# 16-ECP5_FPGA_1.net
KiCad netlist of a schematic drawn in Altium Designer
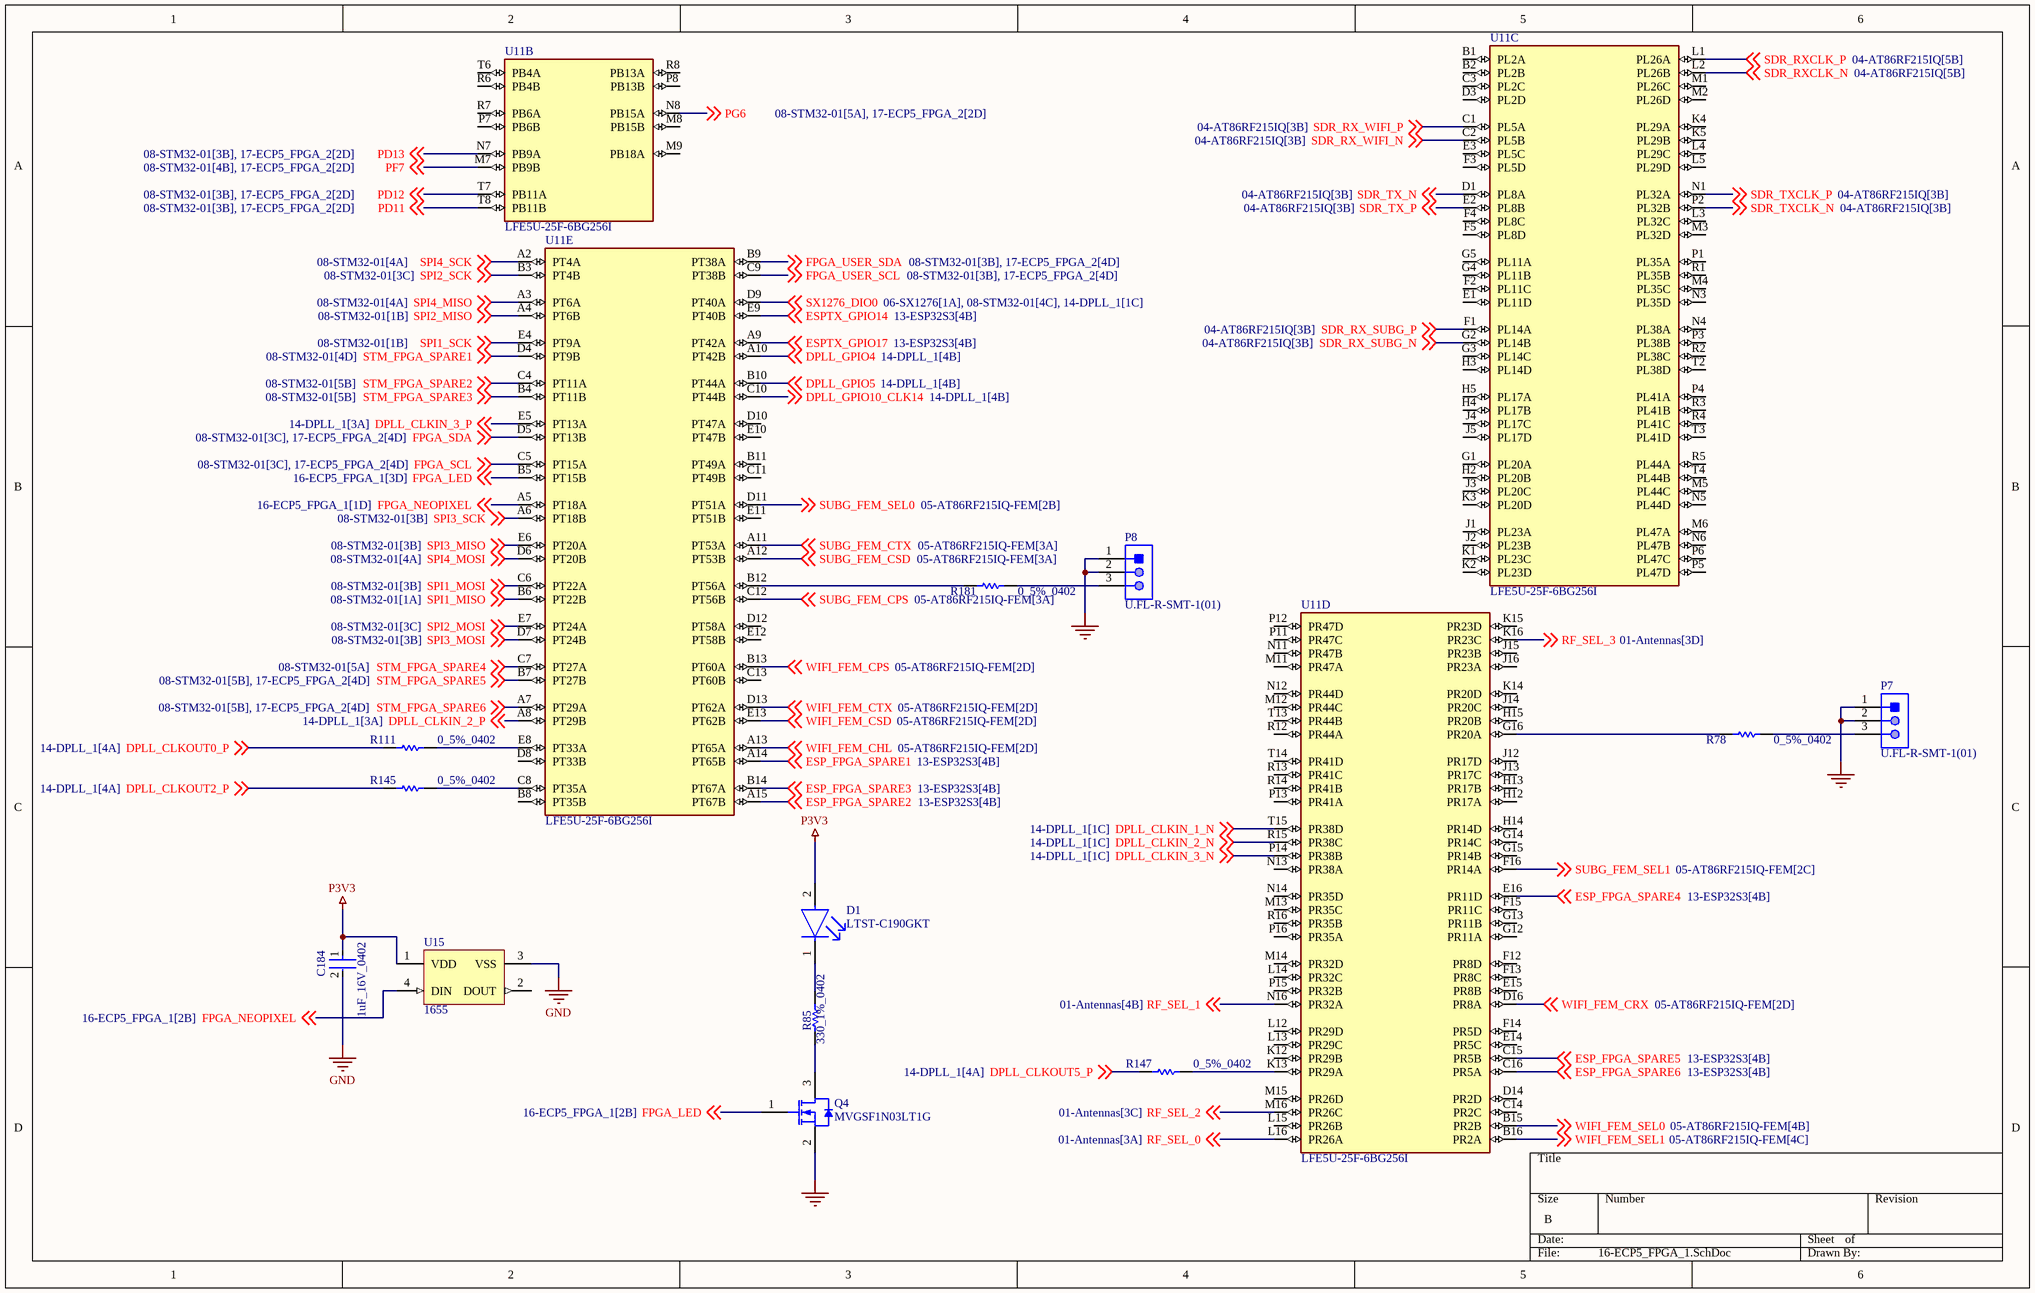
[diagram p0: 16-ECP5_FPGA_1.SchDoc]

(export (version "E")
  (design (tool "Eeschema 10.0.6"))
  (components
    (comp (ref "C184")
      (value "1uF_16V_0402")
      (footprint "FP-0402-L_1_0_0_05-W_0_5-IPC_A")
      (description "None")
      (fields (field (name "TOLERANCE") "10%"))
      (libsource (lib "Altium Content Vault") (part "b4654b650e69147ec39a6b967a45e02"))
    )
    (comp (ref "D1")
      (value "LTST-C190GKT")
      (footprint "FP-LTST-C190GKT-MFG")
      (description "LED GREEN CLEAR CHIP SMD")
      (fields (field (name "VOLTAGE") "2V"))
      (libsource (lib "Altium Content Vault") (part "8706943c75ba83719d021d2fdc84c58"))
    )
    (comp (ref "P7")
      (value "U.FL-R-SMT-1(01)")
      (footprint "HRS-U.FL-R-SMT-3_V")
      (description "Ultra Small Coaxial Connector, 6 GHz, -40 to 90 degC, 3-Pin SMD, RoHS, Bulk")
      (fields (field (name "MANUFACTURER") "Hirose Electric"))
      (libsource (lib "Altium Content Vault") (part "CN-1P-M-R3"))
    )
    (comp (ref "P8")
      (value "U.FL-R-SMT-1(01)")
      (footprint "HRS-U.FL-R-SMT-3_V")
      (description "Ultra Small Coaxial Connector, 6 GHz, -40 to 90 degC, 3-Pin SMD, RoHS, Bulk")
      (fields (field (name "MANUFACTURER") "Hirose Electric"))
      (libsource (lib "Altium Content Vault") (part "CN-1P-M-R3"))
    )
    (comp (ref "Q4")
      (value "MVGSF1N03LT1G")
      (footprint "ONSC-SOT-23-3-318-08_V")
      (description "Power MOSFET, 30 V, 2.1 A, Single N-Channel, 3-Pin SOT-23, Pb-Free, Tape and Reel")
      (fields (field (name "MANUFACTURER") "On Semiconductor"))
      (libsource (lib "Altium Content Vault") (part "ONSC-NMOS-G1S2D3-3"))
    )
    (comp (ref "R78")
      (value "0_5%_0402")
      (footprint "RESC1005X40X25NL05T10")
      (fields (field (name "MANUFACTURER") "Panasonic") (field (name "PART NUMBER") "ERJ-U020R00X"))
      (libsource (lib "Altium Content Vault") (part "RES"))
    )
    (comp (ref "R85")
      (value "330_1%_0402")
      (footprint "RESC1005X40X25NL10T10")
      (fields (field (name "MANUFACTURER") "Panasonic") (field (name "PART NUMBER") "ERA-2AED331X"))
      (libsource (lib "Altium Content Vault") (part "RES"))
    )
    (comp (ref "R111")
      (value "0_5%_0402")
      (footprint "RESC1005X40X25NL05T10")
      (fields (field (name "MANUFACTURER") "Panasonic") (field (name "PART NUMBER") "ERJ-U020R00X"))
      (libsource (lib "Altium Content Vault") (part "RES"))
    )
    (comp (ref "R145")
      (value "0_5%_0402")
      (footprint "RESC1005X40X25NL05T10")
      (fields (field (name "MANUFACTURER") "Panasonic") (field (name "PART NUMBER") "ERJ-U020R00X"))
      (libsource (lib "Altium Content Vault") (part "RES"))
    )
    (comp (ref "R147")
      (value "0_5%_0402")
      (footprint "RESC1005X40X25NL05T10")
      (fields (field (name "MANUFACTURER") "Panasonic") (field (name "PART NUMBER") "ERJ-U020R00X"))
      (libsource (lib "Altium Content Vault") (part "RES"))
    )
    (comp (ref "R181")
      (value "0_5%_0402")
      (footprint "RESC1005X40X25NL05T10")
      (fields (field (name "MANUFACTURER") "Panasonic") (field (name "PART NUMBER") "ERJ-U020R00X"))
      (libsource (lib "Altium Content Vault") (part "RES"))
    )
    (comp (ref "U11")
      (value "LFE5U-25F-6BG256I")
      (footprint "FP-LFE5U-25F-6BG256I-MFG")
      (description "IC FPGA 197 I/O 256CABGA")
      (libsource (lib "Altium Content Vault") (part "bfd34961a1b5a598594aee4faf9689d"))
    )
    (comp (ref "U15")
      (value "1655")
      (footprint "ADA-RGB-1655_V")
      (fields (field (name "MANUFACTURER") "Adafruit-Industries-LLC"))
      (libsource (lib "Altium Content Vault") (part "ADA-RGB-1655-4"))
    )
  )
  (nets
    (net (code "1") (name "DPLL_CLKIN_1_N") (class "Default")
      (node (ref "U11") (pin "T15") (pinfunction "PR38D_T15") (pintype "bidirectional"))
    )
    (net (code "2") (name "DPLL_CLKIN_2_N") (class "Default")
      (node (ref "U11") (pin "R15") (pinfunction "PR38C_R15") (pintype "bidirectional"))
    )
    (net (code "3") (name "DPLL_CLKIN_2_P") (class "Default")
      (node (ref "U11") (pin "A8") (pinfunction "PT29B_A8") (pintype "bidirectional"))
    )
    (net (code "4") (name "DPLL_CLKIN_3_N") (class "Default")
      (node (ref "U11") (pin "P14") (pinfunction "PR38B_P14") (pintype "bidirectional"))
    )
    (net (code "5") (name "DPLL_CLKIN_3_P") (class "Default")
      (node (ref "U11") (pin "E5") (pinfunction "PT13A_E5") (pintype "bidirectional"))
    )
    (net (code "6") (name "DPLL_CLKOUT0_P") (class "Default")
      (node (ref "R111") (pin "1") (pinfunction "1_1") (pintype "passive"))
    )
    (net (code "7") (name "DPLL_CLKOUT2_P") (class "Default")
      (node (ref "R145") (pin "1") (pinfunction "1_1") (pintype "passive"))
    )
    (net (code "8") (name "DPLL_CLKOUT5_P") (class "Default")
      (node (ref "R147") (pin "1") (pinfunction "1_1") (pintype "passive"))
    )
    (net (code "9") (name "DPLL_GPIO4") (class "Default")
      (node (ref "U11") (pin "A10") (pinfunction "PT42B_A10") (pintype "bidirectional"))
    )
    (net (code "10") (name "DPLL_GPIO5") (class "Default")
      (node (ref "U11") (pin "B10") (pinfunction "PT44A_B10") (pintype "bidirectional"))
    )
    (net (code "11") (name "DPLL_GPIO10_CLK14") (class "Default")
      (node (ref "U11") (pin "C10") (pinfunction "PT44B_C10") (pintype "bidirectional"))
    )
    (net (code "12") (name "ESPTX_GPIO14") (class "Default")
      (node (ref "U11") (pin "E9") (pinfunction "PT40B_E9") (pintype "bidirectional"))
    )
    (net (code "13") (name "ESPTX_GPIO17") (class "Default")
      (node (ref "U11") (pin "A9") (pinfunction "PT42A_A9") (pintype "bidirectional"))
    )
    (net (code "14") (name "ESP_FPGA_SPARE1") (class "Default")
      (node (ref "U11") (pin "A14") (pinfunction "PT65B_A14") (pintype "bidirectional"))
    )
    (net (code "15") (name "ESP_FPGA_SPARE2") (class "Default")
      (node (ref "U11") (pin "A15") (pinfunction "PT67B_A15") (pintype "bidirectional"))
    )
    (net (code "16") (name "ESP_FPGA_SPARE3") (class "Default")
      (node (ref "U11") (pin "B14") (pinfunction "PT67A_B14") (pintype "bidirectional"))
    )
    (net (code "17") (name "ESP_FPGA_SPARE4") (class "Default")
      (node (ref "U11") (pin "E16") (pinfunction "PR11D_E16") (pintype "bidirectional"))
    )
    (net (code "18") (name "ESP_FPGA_SPARE5") (class "Default")
      (node (ref "U11") (pin "C15") (pinfunction "PR5B_C15") (pintype "bidirectional"))
    )
    (net (code "19") (name "ESP_FPGA_SPARE6") (class "Default")
      (node (ref "U11") (pin "C16") (pinfunction "PR5A_C16") (pintype "bidirectional"))
    )
    (net (code "20") (name "FPGA_LED") (class "Default")
      (node (ref "Q4") (pin "1") (pinfunction "G_1") (pintype "passive"))
      (node (ref "U11") (pin "B5") (pinfunction "PT15B_B5") (pintype "bidirectional"))
    )
    (net (code "21") (name "FPGA_NEOPIXEL") (class "Default")
      (node (ref "U11") (pin "A5") (pinfunction "PT18A_A5") (pintype "bidirectional"))
      (node (ref "U15") (pin "4") (pinfunction "DIN_4") (pintype "input"))
    )
    (net (code "22") (name "FPGA_SCL") (class "Default")
      (node (ref "U11") (pin "C5") (pinfunction "PT15A_C5") (pintype "bidirectional"))
    )
    (net (code "23") (name "FPGA_SDA") (class "Default")
      (node (ref "U11") (pin "D5") (pinfunction "PT13B_D5") (pintype "bidirectional"))
    )
    (net (code "24") (name "FPGA_USER_SCL") (class "Default")
      (node (ref "U11") (pin "C9") (pinfunction "PT38B_C9") (pintype "bidirectional"))
    )
    (net (code "25") (name "FPGA_USER_SDA") (class "Default")
      (node (ref "U11") (pin "B9") (pinfunction "PT38A_B9") (pintype "bidirectional"))
    )
    (net (code "26") (name "GND") (class "Default")
      (node (ref "C184") (pin "2") (pinfunction "2_2") (pintype "passive"))
      (node (ref "P7") (pin "1") (pinfunction "1_1") (pintype "passive"))
      (node (ref "P7") (pin "2") (pinfunction "2_2") (pintype "passive"))
      (node (ref "P8") (pin "1") (pinfunction "1_1") (pintype "passive"))
      (node (ref "P8") (pin "2") (pinfunction "2_2") (pintype "passive"))
      (node (ref "Q4") (pin "2") (pinfunction "S_2") (pintype "passive"))
      (node (ref "U15") (pin "3") (pinfunction "VSS_3") (pintype "power_in"))
    )
    (net (code "27") (name "Net-(D1-C)") (class "Default")
      (node (ref "D1") (pin "1") (pinfunction "C_1") (pintype "passive"))
      (node (ref "R85") (pin "2") (pinfunction "2_2") (pintype "passive"))
    )
    (net (code "28") (name "Net-(P7-Pad3)") (class "Default")
      (node (ref "P7") (pin "3") (pinfunction "3_3") (pintype "passive"))
      (node (ref "R78") (pin "2") (pinfunction "2_2") (pintype "passive"))
    )
    (net (code "29") (name "Net-(P8-Pad3)") (class "Default")
      (node (ref "P8") (pin "3") (pinfunction "3_3") (pintype "passive"))
      (node (ref "R181") (pin "2") (pinfunction "2_2") (pintype "passive"))
    )
    (net (code "30") (name "Net-(Q4-D)") (class "Default")
      (node (ref "Q4") (pin "3") (pinfunction "D_3") (pintype "passive"))
      (node (ref "R85") (pin "1") (pinfunction "1_1") (pintype "passive"))
    )
    (net (code "31") (name "Net-(U11D-PR20A)") (class "Default")
      (node (ref "R78") (pin "1") (pinfunction "1_1") (pintype "passive"))
      (node (ref "U11") (pin "G16") (pinfunction "PR20A_G16") (pintype "bidirectional"))
    )
    (net (code "32") (name "Net-(U11D-PR29A)") (class "Default")
      (node (ref "R147") (pin "2") (pinfunction "2_2") (pintype "passive"))
      (node (ref "U11") (pin "K13") (pinfunction "PR29A_K13") (pintype "bidirectional"))
    )
    (net (code "33") (name "Net-(U11E-PT33A)") (class "Default")
      (node (ref "R111") (pin "2") (pinfunction "2_2") (pintype "passive"))
      (node (ref "U11") (pin "E8") (pinfunction "PT33A_E8") (pintype "bidirectional"))
    )
    (net (code "34") (name "Net-(U11E-PT35A)") (class "Default")
      (node (ref "R145") (pin "2") (pinfunction "2_2") (pintype "passive"))
      (node (ref "U11") (pin "C8") (pinfunction "PT35A_C8") (pintype "bidirectional"))
    )
    (net (code "35") (name "Net-(U11E-PT56A)") (class "Default")
      (node (ref "R181") (pin "1") (pinfunction "1_1") (pintype "passive"))
      (node (ref "U11") (pin "B12") (pinfunction "PT56A_B12") (pintype "bidirectional"))
    )
    (net (code "36") (name "P3V3") (class "Default")
      (node (ref "C184") (pin "1") (pinfunction "1_1") (pintype "passive"))
      (node (ref "D1") (pin "2") (pinfunction "A_2") (pintype "passive"))
      (node (ref "U15") (pin "1") (pinfunction "VDD_1") (pintype "power_in"))
    )
    (net (code "37") (name "PD11") (class "Default")
      (node (ref "U11") (pin "T8") (pinfunction "PB11B_T8") (pintype "bidirectional"))
    )
    (net (code "38") (name "PD12") (class "Default")
      (node (ref "U11") (pin "T7") (pinfunction "PB11A_T7") (pintype "bidirectional"))
    )
    (net (code "39") (name "PD13") (class "Default")
      (node (ref "U11") (pin "N7") (pinfunction "PB9A_N7") (pintype "bidirectional"))
    )
    (net (code "40") (name "PF7") (class "Default")
      (node (ref "U11") (pin "M7") (pinfunction "PB9B_M7") (pintype "bidirectional"))
    )
    (net (code "41") (name "PG6") (class "Default")
      (node (ref "U11") (pin "N8") (pinfunction "PB15A_N8") (pintype "bidirectional"))
    )
    (net (code "42") (name "RF_SEL_0") (class "Default")
      (node (ref "U11") (pin "L16") (pinfunction "PR26A_L16") (pintype "bidirectional"))
    )
    (net (code "43") (name "RF_SEL_1") (class "Default")
      (node (ref "U11") (pin "N16") (pinfunction "PR32A_N16") (pintype "bidirectional"))
    )
    (net (code "44") (name "RF_SEL_2") (class "Default")
      (node (ref "U11") (pin "M16") (pinfunction "PR26C_M16") (pintype "bidirectional"))
    )
    (net (code "45") (name "RF_SEL_3") (class "Default")
      (node (ref "U11") (pin "K16") (pinfunction "PR23C_K16") (pintype "bidirectional"))
    )
    (net (code "46") (name "SDR_RXCLK_N") (class "Default")
      (node (ref "U11") (pin "L2") (pinfunction "PL26B_L2") (pintype "bidirectional"))
    )
    (net (code "47") (name "SDR_RXCLK_P") (class "Default")
      (node (ref "U11") (pin "L1") (pinfunction "PL26A_L1") (pintype "bidirectional"))
    )
    (net (code "48") (name "SDR_RX_SUBG_N") (class "Default")
      (node (ref "U11") (pin "G2") (pinfunction "PL14B_G2") (pintype "bidirectional"))
    )
    (net (code "49") (name "SDR_RX_SUBG_P") (class "Default")
      (node (ref "U11") (pin "F1") (pinfunction "PL14A_F1") (pintype "bidirectional"))
    )
    (net (code "50") (name "SDR_RX_WIFI_N") (class "Default")
      (node (ref "U11") (pin "C2") (pinfunction "PL5B_C2") (pintype "bidirectional"))
    )
    (net (code "51") (name "SDR_RX_WIFI_P") (class "Default")
      (node (ref "U11") (pin "C1") (pinfunction "PL5A_C1") (pintype "bidirectional"))
    )
    (net (code "52") (name "SDR_TXCLK_N") (class "Default")
      (node (ref "U11") (pin "P2") (pinfunction "PL32B_P2") (pintype "bidirectional"))
    )
    (net (code "53") (name "SDR_TXCLK_P") (class "Default")
      (node (ref "U11") (pin "N1") (pinfunction "PL32A_N1") (pintype "bidirectional"))
    )
    (net (code "54") (name "SDR_TX_N") (class "Default")
      (node (ref "U11") (pin "D1") (pinfunction "PL8A_D1") (pintype "bidirectional"))
    )
    (net (code "55") (name "SDR_TX_P") (class "Default")
      (node (ref "U11") (pin "E2") (pinfunction "PL8B_E2") (pintype "bidirectional"))
    )
    (net (code "56") (name "SPI1_MISO") (class "Default")
      (node (ref "U11") (pin "B6") (pinfunction "PT22B_B6") (pintype "bidirectional"))
    )
    (net (code "57") (name "SPI1_MOSI") (class "Default")
      (node (ref "U11") (pin "C6") (pinfunction "PT22A_C6") (pintype "bidirectional"))
    )
    (net (code "58") (name "SPI1_SCK") (class "Default")
      (node (ref "U11") (pin "E4") (pinfunction "PT9A_E4") (pintype "bidirectional"))
    )
    (net (code "59") (name "SPI2_MISO") (class "Default")
      (node (ref "U11") (pin "A4") (pinfunction "PT6B_A4") (pintype "bidirectional"))
    )
    (net (code "60") (name "SPI2_MOSI") (class "Default")
      (node (ref "U11") (pin "E7") (pinfunction "PT24A_E7") (pintype "bidirectional"))
    )
    (net (code "61") (name "SPI2_SCK") (class "Default")
      (node (ref "U11") (pin "B3") (pinfunction "PT4B_B3") (pintype "bidirectional"))
    )
    (net (code "62") (name "SPI3_MISO") (class "Default")
      (node (ref "U11") (pin "E6") (pinfunction "PT20A_E6") (pintype "bidirectional"))
    )
    (net (code "63") (name "SPI3_MOSI") (class "Default")
      (node (ref "U11") (pin "D7") (pinfunction "PT24B_D7") (pintype "bidirectional"))
    )
    (net (code "64") (name "SPI3_SCK") (class "Default")
      (node (ref "U11") (pin "A6") (pinfunction "PT18B_A6") (pintype "bidirectional"))
    )
    (net (code "65") (name "SPI4_MISO") (class "Default")
      (node (ref "U11") (pin "A3") (pinfunction "PT6A_A3") (pintype "bidirectional"))
    )
    (net (code "66") (name "SPI4_MOSI") (class "Default")
      (node (ref "U11") (pin "D6") (pinfunction "PT20B_D6") (pintype "bidirectional"))
    )
    (net (code "67") (name "SPI4_SCK") (class "Default")
      (node (ref "U11") (pin "A2") (pinfunction "PT4A_A2") (pintype "bidirectional"))
    )
    (net (code "68") (name "STM_FPGA_SPARE1") (class "Default")
      (node (ref "U11") (pin "D4") (pinfunction "PT9B_D4") (pintype "bidirectional"))
    )
    (net (code "69") (name "STM_FPGA_SPARE2") (class "Default")
      (node (ref "U11") (pin "C4") (pinfunction "PT11A_C4") (pintype "bidirectional"))
    )
    (net (code "70") (name "STM_FPGA_SPARE3") (class "Default")
      (node (ref "U11") (pin "B4") (pinfunction "PT11B_B4") (pintype "bidirectional"))
    )
    (net (code "71") (name "STM_FPGA_SPARE4") (class "Default")
      (node (ref "U11") (pin "C7") (pinfunction "PT27A_C7") (pintype "bidirectional"))
    )
    (net (code "72") (name "STM_FPGA_SPARE5") (class "Default")
      (node (ref "U11") (pin "B7") (pinfunction "PT27B_B7") (pintype "bidirectional"))
    )
    (net (code "73") (name "STM_FPGA_SPARE6") (class "Default")
      (node (ref "U11") (pin "A7") (pinfunction "PT29A_A7") (pintype "bidirectional"))
    )
    (net (code "74") (name "SUBG_FEM_CPS") (class "Default")
      (node (ref "U11") (pin "C12") (pinfunction "PT56B_C12") (pintype "bidirectional"))
    )
    (net (code "75") (name "SUBG_FEM_CSD") (class "Default")
      (node (ref "U11") (pin "A12") (pinfunction "PT53B_A12") (pintype "bidirectional"))
    )
    (net (code "76") (name "SUBG_FEM_CTX") (class "Default")
      (node (ref "U11") (pin "A11") (pinfunction "PT53A_A11") (pintype "bidirectional"))
    )
    (net (code "77") (name "SUBG_FEM_SEL0") (class "Default")
      (node (ref "U11") (pin "D11") (pinfunction "PT51A_D11") (pintype "bidirectional"))
    )
    (net (code "78") (name "SUBG_FEM_SEL1") (class "Default")
      (node (ref "U11") (pin "F16") (pinfunction "PR14A_F16") (pintype "bidirectional"))
    )
    (net (code "79") (name "SX1276_DIO0") (class "Default")
      (node (ref "U11") (pin "D9") (pinfunction "PT40A_D9") (pintype "bidirectional"))
    )
    (net (code "80") (name "WIFI_FEM_CHL") (class "Default")
      (node (ref "U11") (pin "A13") (pinfunction "PT65A_A13") (pintype "bidirectional"))
    )
    (net (code "81") (name "WIFI_FEM_CPS") (class "Default")
      (node (ref "U11") (pin "B13") (pinfunction "PT60A_B13") (pintype "bidirectional"))
    )
    (net (code "82") (name "WIFI_FEM_CRX") (class "Default")
      (node (ref "U11") (pin "D16") (pinfunction "PR8A_D16") (pintype "bidirectional"))
    )
    (net (code "83") (name "WIFI_FEM_CSD") (class "Default")
      (node (ref "U11") (pin "E13") (pinfunction "PT62B_E13") (pintype "bidirectional"))
    )
    (net (code "84") (name "WIFI_FEM_CTX") (class "Default")
      (node (ref "U11") (pin "D13") (pinfunction "PT62A_D13") (pintype "bidirectional"))
    )
    (net (code "85") (name "WIFI_FEM_SEL0") (class "Default")
      (node (ref "U11") (pin "B15") (pinfunction "PR2B_B15") (pintype "bidirectional"))
    )
    (net (code "86") (name "WIFI_FEM_SEL1") (class "Default")
      (node (ref "U11") (pin "B16") (pinfunction "PR2A_B16") (pintype "bidirectional"))
    )
    (net (code "87") (name "unconnected-(U11B-PB4A-PadT6)") (class "Default")
      (node (ref "U11") (pin "T6") (pinfunction "PB4A_T6") (pintype "bidirectional"))
    )
    (net (code "88") (name "unconnected-(U11B-PB4B-PadR6)") (class "Default")
      (node (ref "U11") (pin "R6") (pinfunction "PB4B_R6") (pintype "bidirectional"))
    )
    (net (code "89") (name "unconnected-(U11B-PB6A-PadR7)") (class "Default")
      (node (ref "U11") (pin "R7") (pinfunction "PB6A_R7") (pintype "bidirectional"))
    )
    (net (code "90") (name "unconnected-(U11B-PB6B-PadP7)") (class "Default")
      (node (ref "U11") (pin "P7") (pinfunction "PB6B_P7") (pintype "bidirectional"))
    )
    (net (code "91") (name "unconnected-(U11B-PB13A-PadR8)") (class "Default")
      (node (ref "U11") (pin "R8") (pinfunction "PB13A_R8") (pintype "bidirectional"))
    )
    (net (code "92") (name "unconnected-(U11B-PB13B-PadP8)") (class "Default")
      (node (ref "U11") (pin "P8") (pinfunction "PB13B_P8") (pintype "bidirectional"))
    )
    (net (code "93") (name "unconnected-(U11B-PB15B-PadM8)") (class "Default")
      (node (ref "U11") (pin "M8") (pinfunction "PB15B_M8") (pintype "bidirectional"))
    )
    (net (code "94") (name "unconnected-(U11B-PB18A-PadM9)") (class "Default")
      (node (ref "U11") (pin "M9") (pinfunction "PB18A_M9") (pintype "bidirectional"))
    )
    (net (code "95") (name "unconnected-(U11C-PL2A-PadB1)") (class "Default")
      (node (ref "U11") (pin "B1") (pinfunction "PL2A_B1") (pintype "bidirectional"))
    )
    (net (code "96") (name "unconnected-(U11C-PL2B-PadB2)") (class "Default")
      (node (ref "U11") (pin "B2") (pinfunction "PL2B_B2") (pintype "bidirectional"))
    )
    (net (code "97") (name "unconnected-(U11C-PL2C-PadC3)") (class "Default")
      (node (ref "U11") (pin "C3") (pinfunction "PL2C_C3") (pintype "bidirectional"))
    )
    (net (code "98") (name "unconnected-(U11C-PL2D-PadD3)") (class "Default")
      (node (ref "U11") (pin "D3") (pinfunction "PL2D_D3") (pintype "bidirectional"))
    )
    (net (code "99") (name "unconnected-(U11C-PL5C-PadE3)") (class "Default")
      (node (ref "U11") (pin "E3") (pinfunction "PL5C_E3") (pintype "bidirectional"))
    )
    (net (code "100") (name "unconnected-(U11C-PL5D-PadF3)") (class "Default")
      (node (ref "U11") (pin "F3") (pinfunction "PL5D_F3") (pintype "bidirectional"))
    )
    (net (code "101") (name "unconnected-(U11C-PL8C-PadF4)") (class "Default")
      (node (ref "U11") (pin "F4") (pinfunction "PL8C_F4") (pintype "bidirectional"))
    )
    (net (code "102") (name "unconnected-(U11C-PL8D-PadF5)") (class "Default")
      (node (ref "U11") (pin "F5") (pinfunction "PL8D_F5") (pintype "bidirectional"))
    )
    (net (code "103") (name "unconnected-(U11C-PL11A-PadG5)") (class "Default")
      (node (ref "U11") (pin "G5") (pinfunction "PL11A_G5") (pintype "bidirectional"))
    )
    (net (code "104") (name "unconnected-(U11C-PL11B-PadG4)") (class "Default")
      (node (ref "U11") (pin "G4") (pinfunction "PL11B_G4") (pintype "bidirectional"))
    )
    (net (code "105") (name "unconnected-(U11C-PL11C-PadF2)") (class "Default")
      (node (ref "U11") (pin "F2") (pinfunction "PL11C_F2") (pintype "bidirectional"))
    )
    (net (code "106") (name "unconnected-(U11C-PL11D-PadE1)") (class "Default")
      (node (ref "U11") (pin "E1") (pinfunction "PL11D_E1") (pintype "bidirectional"))
    )
    (net (code "107") (name "unconnected-(U11C-PL14C-PadG3)") (class "Default")
      (node (ref "U11") (pin "G3") (pinfunction "PL14C_G3") (pintype "bidirectional"))
    )
    (net (code "108") (name "unconnected-(U11C-PL14D-PadH3)") (class "Default")
      (node (ref "U11") (pin "H3") (pinfunction "PL14D_H3") (pintype "bidirectional"))
    )
    (net (code "109") (name "unconnected-(U11C-PL17A-PadH5)") (class "Default")
      (node (ref "U11") (pin "H5") (pinfunction "PL17A_H5") (pintype "bidirectional"))
    )
    (net (code "110") (name "unconnected-(U11C-PL17B-PadH4)") (class "Default")
      (node (ref "U11") (pin "H4") (pinfunction "PL17B_H4") (pintype "bidirectional"))
    )
    (net (code "111") (name "unconnected-(U11C-PL17C-PadJ4)") (class "Default")
      (node (ref "U11") (pin "J4") (pinfunction "PL17C_J4") (pintype "bidirectional"))
    )
    (net (code "112") (name "unconnected-(U11C-PL17D-PadJ5)") (class "Default")
      (node (ref "U11") (pin "J5") (pinfunction "PL17D_J5") (pintype "bidirectional"))
    )
    (net (code "113") (name "unconnected-(U11C-PL20A-PadG1)") (class "Default")
      (node (ref "U11") (pin "G1") (pinfunction "PL20A_G1") (pintype "bidirectional"))
    )
    (net (code "114") (name "unconnected-(U11C-PL20B-PadH2)") (class "Default")
      (node (ref "U11") (pin "H2") (pinfunction "PL20B_H2") (pintype "bidirectional"))
    )
    (net (code "115") (name "unconnected-(U11C-PL20C-PadJ3)") (class "Default")
      (node (ref "U11") (pin "J3") (pinfunction "PL20C_J3") (pintype "bidirectional"))
    )
    (net (code "116") (name "unconnected-(U11C-PL20D-PadK3)") (class "Default")
      (node (ref "U11") (pin "K3") (pinfunction "PL20D_K3") (pintype "bidirectional"))
    )
    (net (code "117") (name "unconnected-(U11C-PL23A-PadJ1)") (class "Default")
      (node (ref "U11") (pin "J1") (pinfunction "PL23A_J1") (pintype "bidirectional"))
    )
    (net (code "118") (name "unconnected-(U11C-PL23B-PadJ2)") (class "Default")
      (node (ref "U11") (pin "J2") (pinfunction "PL23B_J2") (pintype "bidirectional"))
    )
    (net (code "119") (name "unconnected-(U11C-PL23C-PadK1)") (class "Default")
      (node (ref "U11") (pin "K1") (pinfunction "PL23C_K1") (pintype "bidirectional"))
    )
    (net (code "120") (name "unconnected-(U11C-PL23D-PadK2)") (class "Default")
      (node (ref "U11") (pin "K2") (pinfunction "PL23D_K2") (pintype "bidirectional"))
    )
    (net (code "121") (name "unconnected-(U11C-PL26C-PadM1)") (class "Default")
      (node (ref "U11") (pin "M1") (pinfunction "PL26C_M1") (pintype "bidirectional"))
    )
    (net (code "122") (name "unconnected-(U11C-PL26D-PadM2)") (class "Default")
      (node (ref "U11") (pin "M2") (pinfunction "PL26D_M2") (pintype "bidirectional"))
    )
    (net (code "123") (name "unconnected-(U11C-PL29A-PadK4)") (class "Default")
      (node (ref "U11") (pin "K4") (pinfunction "PL29A_K4") (pintype "bidirectional"))
    )
    (net (code "124") (name "unconnected-(U11C-PL29B-PadK5)") (class "Default")
      (node (ref "U11") (pin "K5") (pinfunction "PL29B_K5") (pintype "bidirectional"))
    )
    (net (code "125") (name "unconnected-(U11C-PL29C-PadL4)") (class "Default")
      (node (ref "U11") (pin "L4") (pinfunction "PL29C_L4") (pintype "bidirectional"))
    )
    (net (code "126") (name "unconnected-(U11C-PL29D-PadL5)") (class "Default")
      (node (ref "U11") (pin "L5") (pinfunction "PL29D_L5") (pintype "bidirectional"))
    )
    (net (code "127") (name "unconnected-(U11C-PL32C-PadL3)") (class "Default")
      (node (ref "U11") (pin "L3") (pinfunction "PL32C_L3") (pintype "bidirectional"))
    )
    (net (code "128") (name "unconnected-(U11C-PL32D-PadM3)") (class "Default")
      (node (ref "U11") (pin "M3") (pinfunction "PL32D_M3") (pintype "bidirectional"))
    )
    (net (code "129") (name "unconnected-(U11C-PL35A-PadP1)") (class "Default")
      (node (ref "U11") (pin "P1") (pinfunction "PL35A_P1") (pintype "bidirectional"))
    )
    (net (code "130") (name "unconnected-(U11C-PL35B-PadR1)") (class "Default")
      (node (ref "U11") (pin "R1") (pinfunction "PL35B_R1") (pintype "bidirectional"))
    )
    (net (code "131") (name "unconnected-(U11C-PL35C-PadM4)") (class "Default")
      (node (ref "U11") (pin "M4") (pinfunction "PL35C_M4") (pintype "bidirectional"))
    )
    (net (code "132") (name "unconnected-(U11C-PL35D-PadN3)") (class "Default")
      (node (ref "U11") (pin "N3") (pinfunction "PL35D_N3") (pintype "bidirectional"))
    )
    (net (code "133") (name "unconnected-(U11C-PL38A-PadN4)") (class "Default")
      (node (ref "U11") (pin "N4") (pinfunction "PL38A_N4") (pintype "bidirectional"))
    )
    (net (code "134") (name "unconnected-(U11C-PL38B-PadP3)") (class "Default")
      (node (ref "U11") (pin "P3") (pinfunction "PL38B_P3") (pintype "bidirectional"))
    )
    (net (code "135") (name "unconnected-(U11C-PL38C-PadR2)") (class "Default")
      (node (ref "U11") (pin "R2") (pinfunction "PL38C_R2") (pintype "bidirectional"))
    )
    (net (code "136") (name "unconnected-(U11C-PL38D-PadT2)") (class "Default")
      (node (ref "U11") (pin "T2") (pinfunction "PL38D_T2") (pintype "bidirectional"))
    )
    (net (code "137") (name "unconnected-(U11C-PL41A-PadP4)") (class "Default")
      (node (ref "U11") (pin "P4") (pinfunction "PL41A_P4") (pintype "bidirectional"))
    )
    (net (code "138") (name "unconnected-(U11C-PL41B-PadR3)") (class "Default")
      (node (ref "U11") (pin "R3") (pinfunction "PL41B_R3") (pintype "bidirectional"))
    )
    (net (code "139") (name "unconnected-(U11C-PL41C-PadR4)") (class "Default")
      (node (ref "U11") (pin "R4") (pinfunction "PL41C_R4") (pintype "bidirectional"))
    )
    (net (code "140") (name "unconnected-(U11C-PL41D-PadT3)") (class "Default")
      (node (ref "U11") (pin "T3") (pinfunction "PL41D_T3") (pintype "bidirectional"))
    )
    (net (code "141") (name "unconnected-(U11C-PL44A-PadR5)") (class "Default")
      (node (ref "U11") (pin "R5") (pinfunction "PL44A_R5") (pintype "bidirectional"))
    )
    (net (code "142") (name "unconnected-(U11C-PL44B-PadT4)") (class "Default")
      (node (ref "U11") (pin "T4") (pinfunction "PL44B_T4") (pintype "bidirectional"))
    )
    (net (code "143") (name "unconnected-(U11C-PL44C-PadM5)") (class "Default")
      (node (ref "U11") (pin "M5") (pinfunction "PL44C_M5") (pintype "bidirectional"))
    )
    (net (code "144") (name "unconnected-(U11C-PL44D-PadN5)") (class "Default")
      (node (ref "U11") (pin "N5") (pinfunction "PL44D_N5") (pintype "bidirectional"))
    )
    (net (code "145") (name "unconnected-(U11C-PL47A-PadM6)") (class "Default")
      (node (ref "U11") (pin "M6") (pinfunction "PL47A_M6") (pintype "bidirectional"))
    )
    (net (code "146") (name "unconnected-(U11C-PL47B-PadN6)") (class "Default")
      (node (ref "U11") (pin "N6") (pinfunction "PL47B_N6") (pintype "bidirectional"))
    )
    (net (code "147") (name "unconnected-(U11C-PL47C-PadP6)") (class "Default")
      (node (ref "U11") (pin "P6") (pinfunction "PL47C_P6") (pintype "bidirectional"))
    )
    (net (code "148") (name "unconnected-(U11C-PL47D-PadP5)") (class "Default")
      (node (ref "U11") (pin "P5") (pinfunction "PL47D_P5") (pintype "bidirectional"))
    )
    (net (code "149") (name "unconnected-(U11D-PR2C-PadC14)") (class "Default")
      (node (ref "U11") (pin "C14") (pinfunction "PR2C_C14") (pintype "bidirectional"))
    )
    (net (code "150") (name "unconnected-(U11D-PR2D-PadD14)") (class "Default")
      (node (ref "U11") (pin "D14") (pinfunction "PR2D_D14") (pintype "bidirectional"))
    )
    (net (code "151") (name "unconnected-(U11D-PR5C-PadE14)") (class "Default")
      (node (ref "U11") (pin "E14") (pinfunction "PR5C_E14") (pintype "bidirectional"))
    )
    (net (code "152") (name "unconnected-(U11D-PR5D-PadF14)") (class "Default")
      (node (ref "U11") (pin "F14") (pinfunction "PR5D_F14") (pintype "bidirectional"))
    )
    (net (code "153") (name "unconnected-(U11D-PR8B-PadE15)") (class "Default")
      (node (ref "U11") (pin "E15") (pinfunction "PR8B_E15") (pintype "bidirectional"))
    )
    (net (code "154") (name "unconnected-(U11D-PR8C-PadF13)") (class "Default")
      (node (ref "U11") (pin "F13") (pinfunction "PR8C_F13") (pintype "bidirectional"))
    )
    (net (code "155") (name "unconnected-(U11D-PR8D-PadF12)") (class "Default")
      (node (ref "U11") (pin "F12") (pinfunction "PR8D_F12") (pintype "bidirectional"))
    )
    (net (code "156") (name "unconnected-(U11D-PR11A-PadG12)") (class "Default")
      (node (ref "U11") (pin "G12") (pinfunction "PR11A_G12") (pintype "bidirectional"))
    )
    (net (code "157") (name "unconnected-(U11D-PR11B-PadG13)") (class "Default")
      (node (ref "U11") (pin "G13") (pinfunction "PR11B_G13") (pintype "bidirectional"))
    )
    (net (code "158") (name "unconnected-(U11D-PR11C-PadF15)") (class "Default")
      (node (ref "U11") (pin "F15") (pinfunction "PR11C_F15") (pintype "bidirectional"))
    )
    (net (code "159") (name "unconnected-(U11D-PR14B-PadG15)") (class "Default")
      (node (ref "U11") (pin "G15") (pinfunction "PR14B_G15") (pintype "bidirectional"))
    )
    (net (code "160") (name "unconnected-(U11D-PR14C-PadG14)") (class "Default")
      (node (ref "U11") (pin "G14") (pinfunction "PR14C_G14") (pintype "bidirectional"))
    )
    (net (code "161") (name "unconnected-(U11D-PR14D-PadH14)") (class "Default")
      (node (ref "U11") (pin "H14") (pinfunction "PR14D_H14") (pintype "bidirectional"))
    )
    (net (code "162") (name "unconnected-(U11D-PR17A-PadH12)") (class "Default")
      (node (ref "U11") (pin "H12") (pinfunction "PR17A_H12") (pintype "bidirectional"))
    )
    (net (code "163") (name "unconnected-(U11D-PR17B-PadH13)") (class "Default")
      (node (ref "U11") (pin "H13") (pinfunction "PR17B_H13") (pintype "bidirectional"))
    )
    (net (code "164") (name "unconnected-(U11D-PR17C-PadJ13)") (class "Default")
      (node (ref "U11") (pin "J13") (pinfunction "PR17C_J13") (pintype "bidirectional"))
    )
    (net (code "165") (name "unconnected-(U11D-PR17D-PadJ12)") (class "Default")
      (node (ref "U11") (pin "J12") (pinfunction "PR17D_J12") (pintype "bidirectional"))
    )
    (net (code "166") (name "unconnected-(U11D-PR20B-PadH15)") (class "Default")
      (node (ref "U11") (pin "H15") (pinfunction "PR20B_H15") (pintype "bidirectional"))
    )
    (net (code "167") (name "unconnected-(U11D-PR20C-PadJ14)") (class "Default")
      (node (ref "U11") (pin "J14") (pinfunction "PR20C_J14") (pintype "bidirectional"))
    )
    (net (code "168") (name "unconnected-(U11D-PR20D-PadK14)") (class "Default")
      (node (ref "U11") (pin "K14") (pinfunction "PR20D_K14") (pintype "bidirectional"))
    )
    (net (code "169") (name "unconnected-(U11D-PR23A-PadJ16)") (class "Default")
      (node (ref "U11") (pin "J16") (pinfunction "PR23A_J16") (pintype "bidirectional"))
    )
    (net (code "170") (name "unconnected-(U11D-PR23B-PadJ15)") (class "Default")
      (node (ref "U11") (pin "J15") (pinfunction "PR23B_J15") (pintype "bidirectional"))
    )
    (net (code "171") (name "unconnected-(U11D-PR23D-PadK15)") (class "Default")
      (node (ref "U11") (pin "K15") (pinfunction "PR23D_K15") (pintype "bidirectional"))
    )
    (net (code "172") (name "unconnected-(U11D-PR26B-PadL15)") (class "Default")
      (node (ref "U11") (pin "L15") (pinfunction "PR26B_L15") (pintype "bidirectional"))
    )
    (net (code "173") (name "unconnected-(U11D-PR26D-PadM15)") (class "Default")
      (node (ref "U11") (pin "M15") (pinfunction "PR26D_M15") (pintype "bidirectional"))
    )
    (net (code "174") (name "unconnected-(U11D-PR29B-PadK12)") (class "Default")
      (node (ref "U11") (pin "K12") (pinfunction "PR29B_K12") (pintype "bidirectional"))
    )
    (net (code "175") (name "unconnected-(U11D-PR29C-PadL13)") (class "Default")
      (node (ref "U11") (pin "L13") (pinfunction "PR29C_L13") (pintype "bidirectional"))
    )
    (net (code "176") (name "unconnected-(U11D-PR29D-PadL12)") (class "Default")
      (node (ref "U11") (pin "L12") (pinfunction "PR29D_L12") (pintype "bidirectional"))
    )
    (net (code "177") (name "unconnected-(U11D-PR32B-PadP15)") (class "Default")
      (node (ref "U11") (pin "P15") (pinfunction "PR32B_P15") (pintype "bidirectional"))
    )
    (net (code "178") (name "unconnected-(U11D-PR32C-PadL14)") (class "Default")
      (node (ref "U11") (pin "L14") (pinfunction "PR32C_L14") (pintype "bidirectional"))
    )
    (net (code "179") (name "unconnected-(U11D-PR32D-PadM14)") (class "Default")
      (node (ref "U11") (pin "M14") (pinfunction "PR32D_M14") (pintype "bidirectional"))
    )
    (net (code "180") (name "unconnected-(U11D-PR35A-PadP16)") (class "Default")
      (node (ref "U11") (pin "P16") (pinfunction "PR35A_P16") (pintype "bidirectional"))
    )
    (net (code "181") (name "unconnected-(U11D-PR35B-PadR16)") (class "Default")
      (node (ref "U11") (pin "R16") (pinfunction "PR35B_R16") (pintype "bidirectional"))
    )
    (net (code "182") (name "unconnected-(U11D-PR35C-PadM13)") (class "Default")
      (node (ref "U11") (pin "M13") (pinfunction "PR35C_M13") (pintype "bidirectional"))
    )
    (net (code "183") (name "unconnected-(U11D-PR35D-PadN14)") (class "Default")
      (node (ref "U11") (pin "N14") (pinfunction "PR35D_N14") (pintype "bidirectional"))
    )
    (net (code "184") (name "unconnected-(U11D-PR38A-PadN13)") (class "Default")
      (node (ref "U11") (pin "N13") (pinfunction "PR38A_N13") (pintype "bidirectional"))
    )
    (net (code "185") (name "unconnected-(U11D-PR41A-PadP13)") (class "Default")
      (node (ref "U11") (pin "P13") (pinfunction "PR41A_P13") (pintype "bidirectional"))
    )
    (net (code "186") (name "unconnected-(U11D-PR41B-PadR14)") (class "Default")
      (node (ref "U11") (pin "R14") (pinfunction "PR41B_R14") (pintype "bidirectional"))
    )
    (net (code "187") (name "unconnected-(U11D-PR41C-PadR13)") (class "Default")
      (node (ref "U11") (pin "R13") (pinfunction "PR41C_R13") (pintype "bidirectional"))
    )
    (net (code "188") (name "unconnected-(U11D-PR41D-PadT14)") (class "Default")
      (node (ref "U11") (pin "T14") (pinfunction "PR41D_T14") (pintype "bidirectional"))
    )
    (net (code "189") (name "unconnected-(U11D-PR44A-PadR12)") (class "Default")
      (node (ref "U11") (pin "R12") (pinfunction "PR44A_R12") (pintype "bidirectional"))
    )
    (net (code "190") (name "unconnected-(U11D-PR44B-PadT13)") (class "Default")
      (node (ref "U11") (pin "T13") (pinfunction "PR44B_T13") (pintype "bidirectional"))
    )
    (net (code "191") (name "unconnected-(U11D-PR44C-PadM12)") (class "Default")
      (node (ref "U11") (pin "M12") (pinfunction "PR44C_M12") (pintype "bidirectional"))
    )
    (net (code "192") (name "unconnected-(U11D-PR44D-PadN12)") (class "Default")
      (node (ref "U11") (pin "N12") (pinfunction "PR44D_N12") (pintype "bidirectional"))
    )
    (net (code "193") (name "unconnected-(U11D-PR47A-PadM11)") (class "Default")
      (node (ref "U11") (pin "M11") (pinfunction "PR47A_M11") (pintype "bidirectional"))
    )
    (net (code "194") (name "unconnected-(U11D-PR47B-PadN11)") (class "Default")
      (node (ref "U11") (pin "N11") (pinfunction "PR47B_N11") (pintype "bidirectional"))
    )
    (net (code "195") (name "unconnected-(U11D-PR47C-PadP11)") (class "Default")
      (node (ref "U11") (pin "P11") (pinfunction "PR47C_P11") (pintype "bidirectional"))
    )
    (net (code "196") (name "unconnected-(U11D-PR47D-PadP12)") (class "Default")
      (node (ref "U11") (pin "P12") (pinfunction "PR47D_P12") (pintype "bidirectional"))
    )
    (net (code "197") (name "unconnected-(U11E-PT33B-PadD8)") (class "Default")
      (node (ref "U11") (pin "D8") (pinfunction "PT33B_D8") (pintype "bidirectional"))
    )
    (net (code "198") (name "unconnected-(U11E-PT35B-PadB8)") (class "Default")
      (node (ref "U11") (pin "B8") (pinfunction "PT35B_B8") (pintype "bidirectional"))
    )
    (net (code "199") (name "unconnected-(U11E-PT47A-PadD10)") (class "Default")
      (node (ref "U11") (pin "D10") (pinfunction "PT47A_D10") (pintype "bidirectional"))
    )
    (net (code "200") (name "unconnected-(U11E-PT47B-PadE10)") (class "Default")
      (node (ref "U11") (pin "E10") (pinfunction "PT47B_E10") (pintype "bidirectional"))
    )
    (net (code "201") (name "unconnected-(U11E-PT49A-PadB11)") (class "Default")
      (node (ref "U11") (pin "B11") (pinfunction "PT49A_B11") (pintype "bidirectional"))
    )
    (net (code "202") (name "unconnected-(U11E-PT49B-PadC11)") (class "Default")
      (node (ref "U11") (pin "C11") (pinfunction "PT49B_C11") (pintype "bidirectional"))
    )
    (net (code "203") (name "unconnected-(U11E-PT51B-PadE11)") (class "Default")
      (node (ref "U11") (pin "E11") (pinfunction "PT51B_E11") (pintype "bidirectional"))
    )
    (net (code "204") (name "unconnected-(U11E-PT58A-PadD12)") (class "Default")
      (node (ref "U11") (pin "D12") (pinfunction "PT58A_D12") (pintype "bidirectional"))
    )
    (net (code "205") (name "unconnected-(U11E-PT58B-PadE12)") (class "Default")
      (node (ref "U11") (pin "E12") (pinfunction "PT58B_E12") (pintype "bidirectional"))
    )
    (net (code "206") (name "unconnected-(U11E-PT60B-PadC13)") (class "Default")
      (node (ref "U11") (pin "C13") (pinfunction "PT60B_C13") (pintype "bidirectional"))
    )
    (net (code "207") (name "unconnected-(U15-DOUT-Pad2)") (class "Default")
      (node (ref "U15") (pin "2") (pinfunction "DOUT_2") (pintype "output"))
    )
  )
)
